# design.net
KiCad netlist of a schematic drawn in Altium Designer
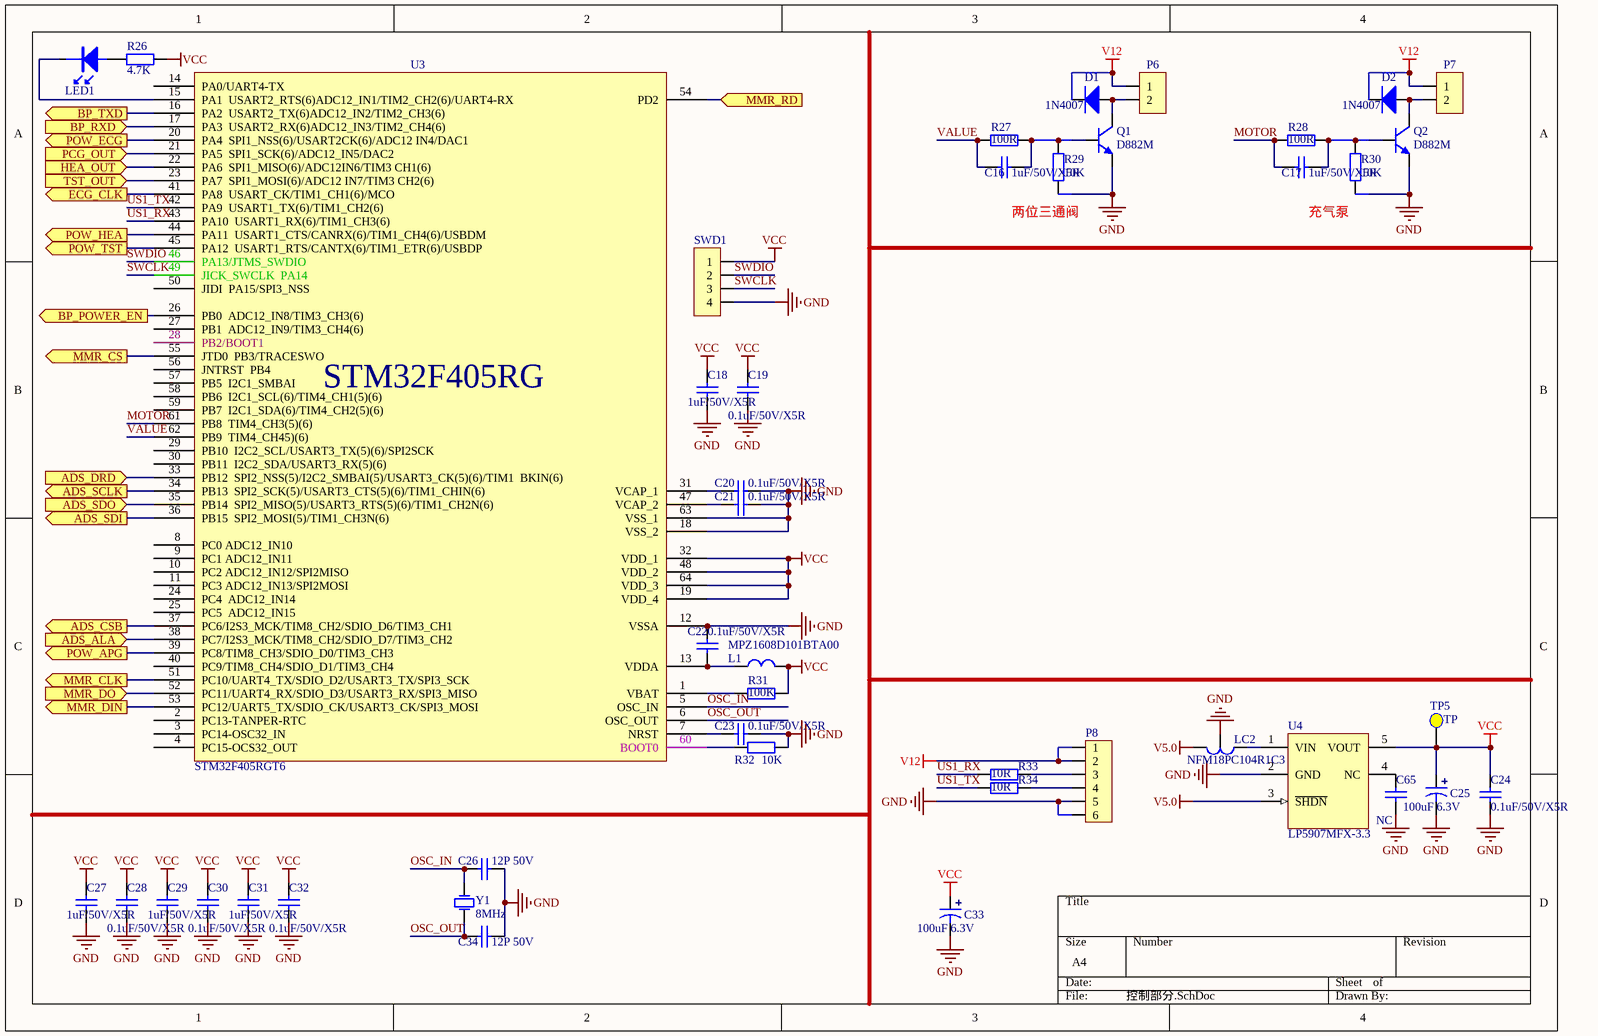
[diagram p0: 控制部分.SchDoc]

(export (version "E")
  (design (tool "Eeschema 10.0.6"))
  (components
    (comp (ref "C16")
      (value "1uF/50V/X5R")
      (footprint "SMD-0603C")
      (description "贴片电容 20%")
      (libsource (lib "XiaoyI") (part "CAP4"))
    )
    (comp (ref "C17")
      (value "1uF/50V/X5R")
      (footprint "SMD-0603C")
      (description "贴片电容 20%")
      (libsource (lib "XiaoyI") (part "CAP4"))
    )
    (comp (ref "C18")
      (value "1uF/50V/X5R")
      (footprint "SMD-0603C")
      (description "贴片电容 20%")
      (libsource (lib "XiaoyI") (part "CAP4"))
    )
    (comp (ref "C19")
      (value "0.1uF/50V/X5R")
      (footprint "SMD-0603C")
      (description "贴片电容 20%")
      (libsource (lib "XiaoyI") (part "CAP4"))
    )
    (comp (ref "C20")
      (value "0.1uF/50V/X5R")
      (footprint "SMD-0603C")
      (description "贴片电容 20%")
      (libsource (lib "XiaoyI") (part "CAP4"))
    )
    (comp (ref "C21")
      (value "0.1uF/50V/X5R")
      (footprint "SMD-0603C")
      (description "贴片电容 20%")
      (libsource (lib "XiaoyI") (part "CAP4"))
    )
    (comp (ref "C22")
      (value "0.1uF/50V/X5R")
      (footprint "SMD-0603C")
      (description "贴片电容 20%")
      (libsource (lib "XiaoyI") (part "CAP4"))
    )
    (comp (ref "C23")
      (value "0.1uF/50V/X5R")
      (footprint "SMD-0603C")
      (description "贴片电容 20%")
      (libsource (lib "XiaoyI") (part "CAP4"))
    )
    (comp (ref "C24")
      (value "0.1uF/50V/X5R")
      (footprint "SMD-0603C")
      (description "贴片电容")
      (libsource (lib "XiaoyI") (part "CAP4"))
    )
    (comp (ref "C25")
      (value "100uF 6.3V")
      (footprint "SMD-3528-B")
      (description "钽电容")
      (libsource (lib "XiaoyI") (part "CAP2"))
    )
    (comp (ref "C26")
      (value "12P 50V")
      (footprint "SMD-0603C")
      (description "贴片电容 20%")
      (libsource (lib "XiaoyI") (part "CAP4"))
    )
    (comp (ref "C27")
      (value "1uF/50V/X5R")
      (footprint "SMD-0603C")
      (description "贴片电容 20%")
      (libsource (lib "XiaoyI") (part "CAP4"))
    )
    (comp (ref "C28")
      (value "0.1uF/50V/X5R")
      (footprint "SMD-0603C")
      (description "贴片电容 20%")
      (libsource (lib "XiaoyI") (part "CAP4"))
    )
    (comp (ref "C29")
      (value "1uF/50V/X5R")
      (footprint "SMD-0603C")
      (description "贴片电容 20%")
      (libsource (lib "XiaoyI") (part "CAP4"))
    )
    (comp (ref "C30")
      (value "0.1uF/50V/X5R")
      (footprint "SMD-0603C")
      (description "贴片电容 20%")
      (libsource (lib "XiaoyI") (part "CAP4"))
    )
    (comp (ref "C31")
      (value "1uF/50V/X5R")
      (footprint "SMD-0603C")
      (description "贴片电容 20%")
      (libsource (lib "XiaoyI") (part "CAP4"))
    )
    (comp (ref "C32")
      (value "0.1uF/50V/X5R")
      (footprint "SMD-0603C")
      (description "贴片电容 20%")
      (libsource (lib "XiaoyI") (part "CAP4"))
    )
    (comp (ref "C33")
      (value "100uF 6.3V")
      (footprint "SMD-3528-B")
      (description "钽电容")
      (libsource (lib "XiaoyI") (part "CAP2"))
    )
    (comp (ref "C34")
      (value "12P 50V")
      (footprint "SMD-0603C")
      (description "贴片电容 20%")
      (libsource (lib "XiaoyI") (part "CAP4"))
    )
    (comp (ref "C65")
      (value "NC")
      (footprint "SMD-0603C")
      (description "贴片电容 10%")
      (libsource (lib "XiaoyI") (part "CAP4"))
    )
    (comp (ref "D1")
      (value "1N4007")
      (footprint "DO-214-AC")
      (description "二极管 M7")
      (libsource (lib "XiaoyI") (part "DIODE2"))
    )
    (comp (ref "D2")
      (value "1N4007")
      (footprint "DO-214-AC")
      (description "二极管 M7")
      (libsource (lib "XiaoyI") (part "DIODE2"))
    )
    (comp (ref "L1")
      (value "MPZ1608D101BTA00")
      (footprint "SMD-0603")
      (description "磁珠电感 100R 100MHz")
      (libsource (lib "XiaoyI") (part "CIZHU1"))
    )
    (comp (ref "LC2")
      (value "NFM18PC104R1C3")
      (footprint "NFM18P-0603")
      (description "LC滤波器")
      (libsource (lib "XiaoyI") (part "SMD-EMIFIL-0603"))
    )
    (comp (ref "LED1")
      (value "蓝")
      (footprint "SMD-0603D")
      (description "LED")
      (libsource (lib "XiaoyI") (part "LED0"))
    )
    (comp (ref "P6")
      (value "VH2.54-2P")
      (footprint "XH-2.54-2P-LI")
      (description "2.54mm- 2P立贴")
      (libsource (lib "XiaoyI") (part "SIP-2"))
    )
    (comp (ref "P7")
      (value "VH2.54-2P")
      (footprint "XH-2.54-2P-LI")
      (description "2.54mm- 2P立贴")
      (libsource (lib "XiaoyI") (part "SIP-2"))
    )
    (comp (ref "P8")
      (value "XH2.54 6P 立贴")
      (footprint "XH-2.54-6P-LI")
      (description "血压计接口")
      (libsource (lib "ABB") (part "SIP-6"))
    )
    (comp (ref "Q1")
      (value "D882M")
      (footprint "SOT-89-3")
      (description "NPN TO252")
      (libsource (lib "XiaoyI") (part "NPN-TO252"))
    )
    (comp (ref "Q2")
      (value "D882M")
      (footprint "SOT-89-3")
      (description "NPN TO252")
      (libsource (lib "XiaoyI") (part "NPN-TO252"))
    )
    (comp (ref "R26")
      (value "4.7K")
      (footprint "SMD-0603")
      (description "贴片电阻")
      (libsource (lib "XiaoyI") (part "RES2"))
    )
    (comp (ref "R27")
      (value "100R")
      (footprint "SMD-0603")
      (description "贴片电阻 5%")
      (libsource (lib "") (part "RES-SOP_1"))
    )
    (comp (ref "R28")
      (value "100R")
      (footprint "SMD-0603")
      (description "贴片电阻 5%")
      (libsource (lib "") (part "RES-SOP_1"))
    )
    (comp (ref "R29")
      (value "10K")
      (footprint "SMD-0603")
      (description "贴片电阻 5%")
      (libsource (lib "XiaoyI") (part "RES-SOP"))
    )
    (comp (ref "R30")
      (value "10K")
      (footprint "SMD-0603")
      (description "贴片电阻 5%")
      (libsource (lib "XiaoyI") (part "RES-SOP"))
    )
    (comp (ref "R31")
      (value "100K")
      (footprint "SMD-0603")
      (description "贴片电阻 5%")
      (libsource (lib "XiaoyI") (part "RES2"))
    )
    (comp (ref "R32")
      (value "10K")
      (footprint "SMD-0603")
      (description "贴片电阻 5%")
      (libsource (lib "") (part "RES2_1"))
    )
    (comp (ref "R33")
      (value "10R")
      (footprint "SMD-0603")
      (description "贴片电阻 5%")
      (libsource (lib "XiaoyI") (part "RES2"))
    )
    (comp (ref "R34")
      (value "10R")
      (footprint "SMD-0603")
      (description "贴片电阻 5%")
      (libsource (lib "XiaoyI") (part "RES2"))
    )
    (comp (ref "SWD1") (value "SIP-4") (footprint "SIP-4") (libsource (lib "XiaoyI") (part "SIP-4")))
    (comp (ref "TP5") (value "TP") (footprint "TP") (libsource (lib "ABB") (part "TP_POINT")))
    (comp (ref "U3")
      (value "STM32F405RGT6")
      (footprint "LQFP64_N")
      (description "MCU")
      (libsource (lib "XiaoyI") (part "STM32F405RG"))
    )
    (comp (ref "U4")
      (value "LP5907MFX-3.3")
      (footprint "SOT23-5")
      (description "LDO")
      (libsource (lib "SYELE") (part "MCP1802"))
    )
    (comp (ref "Y1")
      (value "8MHz")
      (footprint "XTAL-3225-2")
      (description "晶振")
      (libsource (lib "XiaoyI") (part "XTAL"))
    )
  )
  (nets
    (net (code "1") (name "/ADS_ALA") (class "Default")
      (node (ref "U3") (pin "38") (pinfunction "PC7/I2S3_MCK/TIM8_CH2/SDIO_D7/TIM3_CH2_38") (pintype "passive"))
    )
    (net (code "2") (name "/ADS_CSB") (class "Default")
      (node (ref "U3") (pin "37") (pinfunction "PC6/I2S3_MCK/TIM8_CH2/SDIO_D6/TIM3_CH1_37") (pintype "passive"))
    )
    (net (code "3") (name "/ADS_DRD") (class "Default")
      (node (ref "U3") (pin "33") (pinfunction "PB12__SPI2_NSS(5)/I2C2_SMBAI(5)/USART3_CK(5)(6)/TIM1__BKIN(6)_33") (pintype "passive"))
    )
    (net (code "4") (name "/ADS_SCLK") (class "Default")
      (node (ref "U3") (pin "34") (pinfunction "PB13__SPI2_SCK(5)/USART3_CTS(5)(6)/TIM1_CHIN(6)_34") (pintype "passive"))
    )
    (net (code "5") (name "/ADS_SDI") (class "Default")
      (node (ref "U3") (pin "36") (pinfunction "PB15__SPI2_MOSI(5)/TIM1_CH3N(6)_36") (pintype "passive"))
    )
    (net (code "6") (name "/ADS_SDO") (class "Default")
      (node (ref "U3") (pin "35") (pinfunction "PB14__SPI2_MISO(5)/USART3_RTS(5)(6)/TIM1_CH2N(6)_35") (pintype "passive"))
    )
    (net (code "7") (name "/BP_POWER_EN") (class "Default")
      (node (ref "U3") (pin "26") (pinfunction "PB0__ADC12_IN8/TIM3_CH3(6)_26") (pintype "passive"))
    )
    (net (code "8") (name "/BP_RXD") (class "Default")
      (node (ref "U3") (pin "17") (pinfunction "PA3__USART2_RX(6)ADC12_IN3/TIM2_CH4(6)_17") (pintype "passive"))
    )
    (net (code "9") (name "/BP_TXD") (class "Default")
      (node (ref "U3") (pin "16") (pinfunction "PA2__USART2_TX(6)ADC12_IN2/TIM2_CH3(6)_16") (pintype "passive"))
    )
    (net (code "10") (name "/ECG_CLK") (class "Default")
      (node (ref "U3") (pin "41") (pinfunction "PA8__USART_CK/TIM1_CH1(6)/MCO_41") (pintype "passive"))
    )
    (net (code "11") (name "/HEA_OUT") (class "Default")
      (node (ref "U3") (pin "22") (pinfunction "PA6__SPI1_MISO(6)/ADC12IN6/TIM3_CH1(6)_22") (pintype "passive"))
    )
    (net (code "12") (name "/MMR_CLK") (class "Default")
      (node (ref "U3") (pin "51") (pinfunction "PC10/UART4_TX/SDIO_D2/USART3_TX/SPI3_SCK_51") (pintype "passive"))
    )
    (net (code "13") (name "/MMR_CS") (class "Default")
      (node (ref "U3") (pin "55") (pinfunction "JTD0__PB3/TRACESWO_55") (pintype "passive"))
    )
    (net (code "14") (name "/MMR_DIN") (class "Default")
      (node (ref "U3") (pin "53") (pinfunction "PC12/UART5_TX/SDIO_CK/USART3_CK/SPI3_MOSI_53") (pintype "passive"))
    )
    (net (code "15") (name "/MMR_DO") (class "Default")
      (node (ref "U3") (pin "52") (pinfunction "PC11/UART4_RX/SDIO_D3/USART3_RX/SPI3_MISO_52") (pintype "passive"))
    )
    (net (code "16") (name "/MMR_RD") (class "Default")
      (node (ref "U3") (pin "54") (pinfunction "PD2_54") (pintype "passive"))
    )
    (net (code "17") (name "/MOTOR") (class "Default")
      (node (ref "C17") (pin "2") (pinfunction "2_2") (pintype "passive"))
      (node (ref "R28") (pin "2") (pinfunction "2_2") (pintype "passive"))
      (node (ref "U3") (pin "61") (pinfunction "PB8__TIM4_CH3(5)(6)_61") (pintype "passive"))
    )
    (net (code "18") (name "/OSC_IN") (class "Default")
      (node (ref "C26") (pin "2") (pinfunction "2_2") (pintype "passive"))
      (node (ref "U3") (pin "5") (pinfunction "OSC_IN_5") (pintype "passive"))
      (node (ref "Y1") (pin "2") (pinfunction "OSC2_2") (pintype "passive"))
    )
    (net (code "19") (name "/OSC_OUT") (class "Default")
      (node (ref "C34") (pin "2") (pinfunction "2_2") (pintype "passive"))
      (node (ref "U3") (pin "6") (pinfunction "OSC_OUT_6") (pintype "passive"))
      (node (ref "Y1") (pin "1") (pinfunction "OSC1_1") (pintype "passive"))
    )
    (net (code "20") (name "/PCG_OUT") (class "Default")
      (node (ref "U3") (pin "21") (pinfunction "PA5__SPI1_SCK(6)/ADC12_IN5/DAC2_21") (pintype "passive"))
    )
    (net (code "21") (name "/POW_APG") (class "Default")
      (node (ref "U3") (pin "39") (pinfunction "PC8/TIM8_CH3/SDIO_D0/TIM3_CH3_39") (pintype "passive"))
    )
    (net (code "22") (name "/POW_ECG") (class "Default")
      (node (ref "U3") (pin "20") (pinfunction "PA4__SPI1_NSS(6)/USART2CK(6)/ADC12_IN4/DAC1_20") (pintype "passive"))
    )
    (net (code "23") (name "/POW_HEA") (class "Default")
      (node (ref "U3") (pin "44") (pinfunction "PA11__USART1_CTS/CANRX(6)/TIM1_CH4(6)/USBDM_44") (pintype "passive"))
    )
    (net (code "24") (name "/POW_TST") (class "Default")
      (node (ref "U3") (pin "45") (pinfunction "PA12__USART1_RTS/CANTX(6)/TIM1_ETR(6)/USBDP_45") (pintype "passive"))
    )
    (net (code "25") (name "/SWCLK") (class "Default")
      (node (ref "SWD1") (pin "3") (pinfunction "3_3") (pintype "passive"))
      (node (ref "U3") (pin "49") (pinfunction "JICK_SWCLK__PA14_49") (pintype "passive"))
    )
    (net (code "26") (name "/SWDIO") (class "Default")
      (node (ref "SWD1") (pin "2") (pinfunction "2_2") (pintype "passive"))
      (node (ref "U3") (pin "46") (pinfunction "PA13/JTMS_SWDIO_46") (pintype "passive"))
    )
    (net (code "27") (name "/TST_OUT") (class "Default")
      (node (ref "U3") (pin "23") (pinfunction "PA7__SPI1_MOSI(6)/ADC12_IN7/TIM3_CH2(6)_23") (pintype "passive"))
    )
    (net (code "28") (name "/US1_RX") (class "Default")
      (node (ref "R33") (pin "2") (pinfunction "2_2") (pintype "passive"))
      (node (ref "U3") (pin "43") (pinfunction "PA10__USART1_RX(6)/TIM1_CH3(6)_43") (pintype "passive"))
    )
    (net (code "29") (name "/US1_TX") (class "Default")
      (node (ref "R34") (pin "2") (pinfunction "2_2") (pintype "passive"))
      (node (ref "U3") (pin "42") (pinfunction "PA9__USART1_TX(6)/TIM1_CH2(6)_42") (pintype "passive"))
    )
    (net (code "30") (name "/VALUE") (class "Default")
      (node (ref "C16") (pin "2") (pinfunction "2_2") (pintype "passive"))
      (node (ref "R27") (pin "2") (pinfunction "2_2") (pintype "passive"))
      (node (ref "U3") (pin "62") (pinfunction "PB9__TIM4_CH45)(6)_62") (pintype "passive"))
    )
    (net (code "31") (name "GND") (class "Default")
      (node (ref "C18") (pin "1") (pinfunction "1_1") (pintype "passive"))
      (node (ref "C19") (pin "1") (pinfunction "1_1") (pintype "passive"))
      (node (ref "C20") (pin "1") (pinfunction "1_1") (pintype "passive"))
      (node (ref "C21") (pin "1") (pinfunction "1_1") (pintype "passive"))
      (node (ref "C22") (pin "1") (pinfunction "1_1") (pintype "passive"))
      (node (ref "C23") (pin "2") (pinfunction "2_2") (pintype "passive"))
      (node (ref "C24") (pin "1") (pinfunction "1_1") (pintype "passive"))
      (node (ref "C25") (pin "2") (pinfunction "2_2") (pintype "passive"))
      (node (ref "C26") (pin "1") (pinfunction "1_1") (pintype "passive"))
      (node (ref "C27") (pin "1") (pinfunction "1_1") (pintype "passive"))
      (node (ref "C28") (pin "1") (pinfunction "1_1") (pintype "passive"))
      (node (ref "C29") (pin "1") (pinfunction "1_1") (pintype "passive"))
      (node (ref "C30") (pin "1") (pinfunction "1_1") (pintype "passive"))
      (node (ref "C31") (pin "1") (pinfunction "1_1") (pintype "passive"))
      (node (ref "C32") (pin "1") (pinfunction "1_1") (pintype "passive"))
      (node (ref "C33") (pin "2") (pinfunction "2_2") (pintype "passive"))
      (node (ref "C34") (pin "1") (pinfunction "1_1") (pintype "passive"))
      (node (ref "C65") (pin "1") (pinfunction "1_1") (pintype "passive"))
      (node (ref "LC2") (pin "2") (pinfunction "2_2") (pintype "passive"))
      (node (ref "P8") (pin "5") (pinfunction "5_5") (pintype "passive"))
      (node (ref "P8") (pin "6") (pinfunction "6_6") (pintype "passive"))
      (node (ref "Q1") (pin "3") (pinfunction "E_3") (pintype "passive"))
      (node (ref "Q2") (pin "3") (pinfunction "E_3") (pintype "passive"))
      (node (ref "R29") (pin "2") (pinfunction "2_2") (pintype "passive"))
      (node (ref "R30") (pin "2") (pinfunction "2_2") (pintype "passive"))
      (node (ref "R32") (pin "2") (pinfunction "2_2") (pintype "passive"))
      (node (ref "SWD1") (pin "4") (pinfunction "4_4") (pintype "passive"))
      (node (ref "U3") (pin "12") (pinfunction "VSSA_12") (pintype "passive"))
      (node (ref "U3") (pin "18") (pinfunction "VSS_2_18") (pintype "passive"))
      (node (ref "U3") (pin "63") (pinfunction "VSS_1_63") (pintype "passive"))
      (node (ref "U4") (pin "2") (pinfunction "GND_2") (pintype "power_in"))
    )
    (net (code "32") (name "Net-(D1-A)") (class "Default")
      (node (ref "D1") (pin "1") (pinfunction "A_1") (pintype "passive"))
      (node (ref "P6") (pin "2") (pinfunction "2_2") (pintype "passive"))
      (node (ref "Q1") (pin "2") (pinfunction "C_2") (pintype "passive"))
    )
    (net (code "33") (name "Net-(D2-A)") (class "Default")
      (node (ref "D2") (pin "1") (pinfunction "A_1") (pintype "passive"))
      (node (ref "P7") (pin "2") (pinfunction "2_2") (pintype "passive"))
      (node (ref "Q2") (pin "2") (pinfunction "C_2") (pintype "passive"))
    )
    (net (code "34") (name "Net-(LED1-Pad1)") (class "Default")
      (node (ref "LED1") (pin "1") (pinfunction "1_1") (pintype "passive"))
      (node (ref "R26") (pin "2") (pinfunction "2_2") (pintype "passive"))
    )
    (net (code "35") (name "Net-(P8-Pad3)") (class "Default")
      (node (ref "P8") (pin "3") (pinfunction "3_3") (pintype "passive"))
      (node (ref "R33") (pin "1") (pinfunction "1_1") (pintype "passive"))
    )
    (net (code "36") (name "Net-(P8-Pad4)") (class "Default")
      (node (ref "P8") (pin "4") (pinfunction "4_4") (pintype "passive"))
      (node (ref "R34") (pin "1") (pinfunction "1_1") (pintype "passive"))
    )
    (net (code "37") (name "Net-(Q1-B)") (class "Default")
      (node (ref "C16") (pin "1") (pinfunction "1_1") (pintype "passive"))
      (node (ref "Q1") (pin "1") (pinfunction "B_1") (pintype "passive"))
      (node (ref "R27") (pin "1") (pinfunction "1_1") (pintype "passive"))
      (node (ref "R29") (pin "1") (pinfunction "1_1") (pintype "passive"))
    )
    (net (code "38") (name "Net-(Q2-B)") (class "Default")
      (node (ref "C17") (pin "1") (pinfunction "1_1") (pintype "passive"))
      (node (ref "Q2") (pin "1") (pinfunction "B_1") (pintype "passive"))
      (node (ref "R28") (pin "1") (pinfunction "1_1") (pintype "passive"))
      (node (ref "R30") (pin "1") (pinfunction "1_1") (pintype "passive"))
    )
    (net (code "39") (name "Net-(U3-BOOT0)") (class "Default")
      (node (ref "R32") (pin "1") (pinfunction "1_1") (pintype "passive"))
      (node (ref "U3") (pin "60") (pinfunction "BOOT0_60") (pintype "passive"))
    )
    (net (code "40") (name "Net-(U3-NRST)") (class "Default")
      (node (ref "C23") (pin "1") (pinfunction "1_1") (pintype "passive"))
      (node (ref "U3") (pin "7") (pinfunction "NRST_7") (pintype "passive"))
    )
    (net (code "41") (name "Net-(U3-PA1__USART2_RTS(6)ADC12_IN1{slash}TIM2_CH2(6){slash}UART4-RX)") (class "Default")
      (node (ref "LED1") (pin "2") (pinfunction "2_2") (pintype "passive"))
      (node (ref "U3") (pin "15") (pinfunction "PA1__USART2_RTS(6)ADC12_IN1/TIM2_CH2(6)/UART4-RX_15") (pintype "passive"))
    )
    (net (code "42") (name "Net-(U3-VBAT)") (class "Default")
      (node (ref "R31") (pin "2") (pinfunction "2_2") (pintype "passive"))
      (node (ref "U3") (pin "1") (pinfunction "VBAT_1") (pintype "passive"))
    )
    (net (code "43") (name "Net-(U3-VCAP_1)") (class "Default")
      (node (ref "C20") (pin "2") (pinfunction "2_2") (pintype "passive"))
      (node (ref "U3") (pin "31") (pinfunction "VCAP_1_31") (pintype "passive"))
    )
    (net (code "44") (name "Net-(U3-VCAP_2)") (class "Default")
      (node (ref "C21") (pin "2") (pinfunction "2_2") (pintype "passive"))
      (node (ref "U3") (pin "47") (pinfunction "VCAP_2_47") (pintype "passive"))
    )
    (net (code "45") (name "Net-(U3-VDDA)") (class "Default")
      (node (ref "C22") (pin "2") (pinfunction "2_2") (pintype "passive"))
      (node (ref "L1") (pin "1") (pinfunction "1_1") (pintype "passive"))
      (node (ref "U3") (pin "13") (pinfunction "VDDA_13") (pintype "passive"))
    )
    (net (code "46") (name "Net-(U4-NC)") (class "Default")
      (node (ref "C65") (pin "2") (pinfunction "2_2") (pintype "passive"))
      (node (ref "U4") (pin "4") (pinfunction "NC_4") (pintype "passive"))
    )
    (net (code "47") (name "Net-(U4-VIN)") (class "Default")
      (node (ref "LC2") (pin "1") (pinfunction "1_1") (pintype "passive"))
      (node (ref "U4") (pin "1") (pinfunction "VIN_1") (pintype "power_in"))
    )
    (net (code "48") (name "V5.0") (class "Default")
      (node (ref "LC2") (pin "3") (pinfunction "3_3") (pintype "passive"))
      (node (ref "U4") (pin "3") (pinfunction "~{SHDN}_3") (pintype "input"))
    )
    (net (code "49") (name "V12") (class "Default")
      (node (ref "D1") (pin "2") (pinfunction "K_2") (pintype "passive"))
      (node (ref "D2") (pin "2") (pinfunction "K_2") (pintype "passive"))
      (node (ref "P6") (pin "1") (pinfunction "1_1") (pintype "passive"))
      (node (ref "P7") (pin "1") (pinfunction "1_1") (pintype "passive"))
      (node (ref "P8") (pin "1") (pinfunction "1_1") (pintype "passive"))
      (node (ref "P8") (pin "2") (pinfunction "2_2") (pintype "passive"))
    )
    (net (code "50") (name "VCC") (class "Default")
      (node (ref "C18") (pin "2") (pinfunction "2_2") (pintype "passive"))
      (node (ref "C19") (pin "2") (pinfunction "2_2") (pintype "passive"))
      (node (ref "C24") (pin "2") (pinfunction "2_2") (pintype "passive"))
      (node (ref "C25") (pin "1") (pinfunction "1_1") (pintype "passive"))
      (node (ref "C27") (pin "2") (pinfunction "2_2") (pintype "passive"))
      (node (ref "C28") (pin "2") (pinfunction "2_2") (pintype "passive"))
      (node (ref "C29") (pin "2") (pinfunction "2_2") (pintype "passive"))
      (node (ref "C30") (pin "2") (pinfunction "2_2") (pintype "passive"))
      (node (ref "C31") (pin "2") (pinfunction "2_2") (pintype "passive"))
      (node (ref "C32") (pin "2") (pinfunction "2_2") (pintype "passive"))
      (node (ref "C33") (pin "1") (pinfunction "1_1") (pintype "passive"))
      (node (ref "L1") (pin "2") (pinfunction "2_2") (pintype "passive"))
      (node (ref "R26") (pin "1") (pinfunction "1_1") (pintype "passive"))
      (node (ref "R31") (pin "1") (pinfunction "1_1") (pintype "passive"))
      (node (ref "SWD1") (pin "1") (pinfunction "1_1") (pintype "passive"))
      (node (ref "TP5") (pin "1") (pinfunction "TP_1") (pintype "power_in"))
      (node (ref "U3") (pin "19") (pinfunction "VDD_4_19") (pintype "passive"))
      (node (ref "U3") (pin "32") (pinfunction "VDD_1_32") (pintype "passive"))
      (node (ref "U3") (pin "48") (pinfunction "VDD_2_48") (pintype "passive"))
      (node (ref "U3") (pin "64") (pinfunction "VDD_3_64") (pintype "passive"))
      (node (ref "U4") (pin "5") (pinfunction "VOUT_5") (pintype "power_in"))
    )
    (net (code "51") (name "unconnected-(U3-JIDI__PA15{slash}SPI3_NSS-Pad50)") (class "Default")
      (node (ref "U3") (pin "50") (pinfunction "JIDI__PA15/SPI3_NSS_50") (pintype "passive"))
    )
    (net (code "52") (name "unconnected-(U3-JNTRST__PB4-Pad56)") (class "Default")
      (node (ref "U3") (pin "56") (pinfunction "JNTRST__PB4_56") (pintype "passive"))
    )
    (net (code "53") (name "unconnected-(U3-PA0{slash}UART4-TX-Pad14)") (class "Default")
      (node (ref "U3") (pin "14") (pinfunction "PA0/UART4-TX_14") (pintype "passive"))
    )
    (net (code "54") (name "unconnected-(U3-PB1__ADC12_IN9{slash}TIM3_CH4(6)-Pad27)") (class "Default")
      (node (ref "U3") (pin "27") (pinfunction "PB1__ADC12_IN9/TIM3_CH4(6)_27") (pintype "passive"))
    )
    (net (code "55") (name "unconnected-(U3-PB2{slash}BOOT1-Pad28)") (class "Default")
      (node (ref "U3") (pin "28") (pinfunction "PB2/BOOT1_28") (pintype "passive"))
    )
    (net (code "56") (name "unconnected-(U3-PB5__I2C1_SMBAI-Pad57)") (class "Default")
      (node (ref "U3") (pin "57") (pinfunction "PB5__I2C1_SMBAI_57") (pintype "passive"))
    )
    (net (code "57") (name "unconnected-(U3-PB6__I2C1_SCL(6){slash}TIM4_CH1(5)(6)-Pad58)") (class "Default")
      (node (ref "U3") (pin "58") (pinfunction "PB6__I2C1_SCL(6)/TIM4_CH1(5)(6)_58") (pintype "passive"))
    )
    (net (code "58") (name "unconnected-(U3-PB7__I2C1_SDA(6){slash}TIM4_CH2(5)(6)-Pad59)") (class "Default")
      (node (ref "U3") (pin "59") (pinfunction "PB7__I2C1_SDA(6)/TIM4_CH2(5)(6)_59") (pintype "passive"))
    )
    (net (code "59") (name "unconnected-(U3-PB10__I2C2_SCL{slash}USART3_TX(5)(6){slash}SPI2SCK-Pad29)") (class "Default")
      (node (ref "U3") (pin "29") (pinfunction "PB10__I2C2_SCL/USART3_TX(5)(6)/SPI2SCK_29") (pintype "passive"))
    )
    (net (code "60") (name "unconnected-(U3-PB11__I2C2_SDA{slash}USART3_RX(5)(6)-Pad30)") (class "Default")
      (node (ref "U3") (pin "30") (pinfunction "PB11__I2C2_SDA/USART3_RX(5)(6)_30") (pintype "passive"))
    )
    (net (code "61") (name "unconnected-(U3-PC0_ADC12_IN10-Pad8)") (class "Default")
      (node (ref "U3") (pin "8") (pinfunction "PC0_ADC12_IN10_8") (pintype "passive"))
    )
    (net (code "62") (name "unconnected-(U3-PC1_ADC12_IN11-Pad9)") (class "Default")
      (node (ref "U3") (pin "9") (pinfunction "PC1_ADC12_IN11_9") (pintype "passive"))
    )
    (net (code "63") (name "unconnected-(U3-PC2_ADC12_IN12{slash}SPI2MISO-Pad10)") (class "Default")
      (node (ref "U3") (pin "10") (pinfunction "PC2_ADC12_IN12/SPI2MISO_10") (pintype "passive"))
    )
    (net (code "64") (name "unconnected-(U3-PC3_ADC12_IN13{slash}SPI2MOSI-Pad11)") (class "Default")
      (node (ref "U3") (pin "11") (pinfunction "PC3_ADC12_IN13/SPI2MOSI_11") (pintype "passive"))
    )
    (net (code "65") (name "unconnected-(U3-PC4__ADC12_IN14-Pad24)") (class "Default")
      (node (ref "U3") (pin "24") (pinfunction "PC4__ADC12_IN14_24") (pintype "passive"))
    )
    (net (code "66") (name "unconnected-(U3-PC5__ADC12_IN15-Pad25)") (class "Default")
      (node (ref "U3") (pin "25") (pinfunction "PC5__ADC12_IN15_25") (pintype "passive"))
    )
    (net (code "67") (name "unconnected-(U3-PC9{slash}TIM8_CH4{slash}SDIO_D1{slash}TIM3_CH4-Pad40)") (class "Default")
      (node (ref "U3") (pin "40") (pinfunction "PC9/TIM8_CH4/SDIO_D1/TIM3_CH4_40") (pintype "passive"))
    )
    (net (code "68") (name "unconnected-(U3-PC13-TANPER-RTC-Pad2)") (class "Default")
      (node (ref "U3") (pin "2") (pinfunction "PC13-TANPER-RTC_2") (pintype "passive"))
    )
    (net (code "69") (name "unconnected-(U3-PC14-OSC32_IN-Pad3)") (class "Default")
      (node (ref "U3") (pin "3") (pinfunction "PC14-OSC32_IN_3") (pintype "passive"))
    )
    (net (code "70") (name "unconnected-(U3-PC15-OCS32_OUT-Pad4)") (class "Default")
      (node (ref "U3") (pin "4") (pinfunction "PC15-OCS32_OUT_4") (pintype "passive"))
    )
  )
)
